# Simple-Bug-BC557.net
KiCad netlist of a schematic drawn in EAGLE
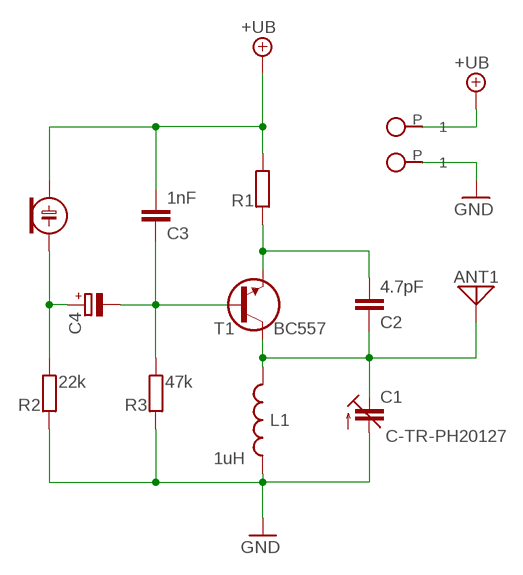
[diagram p0: schematic, sheet 1]

(export (version "E")
  (design (tool "Eeschema 10.0.6"))
  (components
    (comp (ref "+")
      (value "SPAD")
      (footprint "eagle-import:SPAD")
      (libsource (lib "eagle-import") (part "SPAD"))
    )
    (comp (ref "ANT1")
      (value "ANT")
      (footprint "eagle-import:SPAD")
      (libsource (lib "eagle-import") (part "ANT"))
    )
    (comp (ref "C1")
      (value "C-TR-PH20127")
      (footprint "eagle-import:TRIM808-45")
      (libsource (lib "eagle-import") (part "C-TR-PH20127-45-2P23"))
    )
    (comp (ref "C2")
      (value "4.7pF")
      (footprint "eagle-import:C050-020X036")
      (libsource (lib "eagle-import") (part "C050-020X036"))
    )
    (comp (ref "C3")
      (value "1nF")
      (footprint "eagle-import:C050-020X036")
      (libsource (lib "eagle-import") (part "C050-020X036"))
    )
    (comp (ref "C4")
      (value "CPOLE2,5-3")
      (footprint "eagle-import:E2,5-3")
      (libsource (lib "eagle-import") (part "CPOLE2,5-3"))
    )
    (comp (ref "ECM")
      (value "ECM-5")
      (footprint "eagle-import:ECM-5")
      (libsource (lib "eagle-import") (part "ECM-5"))
    )
    (comp (ref "L1")
      (value "1uH")
      (footprint "eagle-import:L-04_7")
      (libsource (lib "eagle-import") (part "L04/7"))
    )
    (comp (ref "R1")
      (value "R0202V")
      (footprint "eagle-import:0202V")
      (libsource (lib "eagle-import") (part "R0202V"))
    )
    (comp (ref "R2")
      (value "22k")
      (footprint "eagle-import:0202_5")
      (libsource (lib "eagle-import") (part "R0202/5"))
    )
    (comp (ref "R3")
      (value "47k")
      (footprint "eagle-import:0202_5")
      (libsource (lib "eagle-import") (part "R0202/5"))
    )
    (comp (ref "T1")
      (value "BC557")
      (footprint "eagle-import:TO92-CBE-A")
      (libsource (lib "eagle-import") (part "BC547CBE-A"))
    )
    (comp (ref "̶̶")
      (value "SPAD")
      (footprint "eagle-import:SPAD")
      (libsource (lib "eagle-import") (part "SPAD"))
    )
  )
  (nets
    (net (code "1") (name "+UB") (class "Default")
      (node (ref "+") (pin "P") (pinfunction "1_P") (pintype "bidirectional"))
      (node (ref "C3") (pin "2") (pinfunction "2_2") (pintype "passive"))
      (node (ref "ECM") (pin "1") (pinfunction "+_1") (pintype "passive"))
      (node (ref "R1") (pin "1") (pinfunction "1_1") (pintype "passive"))
    )
    (net (code "2") (name "GND") (class "Default")
      (node (ref "C1") (pin "2") (pinfunction "A_2") (pintype "passive"))
      (node (ref "L1") (pin "2") (pinfunction "2_2") (pintype "passive"))
      (node (ref "R2") (pin "2") (pinfunction "2_2") (pintype "passive"))
      (node (ref "R3") (pin "2") (pinfunction "2_2") (pintype "passive"))
      (node (ref "̶̶") (pin "P") (pinfunction "1_P") (pintype "bidirectional"))
    )
    (net (code "3") (name "Net-(ANT1-1)") (class "Default")
      (node (ref "ANT1") (pin "P") (pinfunction "1_P") (pintype "output"))
      (node (ref "C1") (pin "3") (pinfunction "E_3") (pintype "passive"))
      (node (ref "C2") (pin "1") (pinfunction "1_1") (pintype "passive"))
      (node (ref "L1") (pin "1") (pinfunction "1_1") (pintype "passive"))
      (node (ref "T1") (pin "C") (pinfunction "C_C") (pintype "passive"))
    )
    (net (code "4") (name "Net-(C2-Pad2)") (class "Default")
      (node (ref "C2") (pin "2") (pinfunction "2_2") (pintype "passive"))
      (node (ref "R1") (pin "2") (pinfunction "2_2") (pintype "passive"))
      (node (ref "T1") (pin "E") (pinfunction "E_E") (pintype "passive"))
    )
    (net (code "5") (name "Net-(C3-Pad1)") (class "Default")
      (node (ref "C3") (pin "1") (pinfunction "1_1") (pintype "passive"))
      (node (ref "C4") (pin "-") (pinfunction "-_-") (pintype "passive"))
      (node (ref "R3") (pin "1") (pinfunction "1_1") (pintype "passive"))
      (node (ref "T1") (pin "B") (pinfunction "B_B") (pintype "passive"))
    )
    (net (code "6") (name "Net-(ECM--)") (class "Default")
      (node (ref "C4") (pin "+") (pinfunction "+_+") (pintype "passive"))
      (node (ref "ECM") (pin "2") (pinfunction "-_2") (pintype "passive"))
      (node (ref "R2") (pin "1") (pinfunction "1_1") (pintype "passive"))
    )
  )
)
